# Sheet_3_3v_2020-09-13_15-20-00.net
KiCad netlist of a schematic drawn in Altium Designer
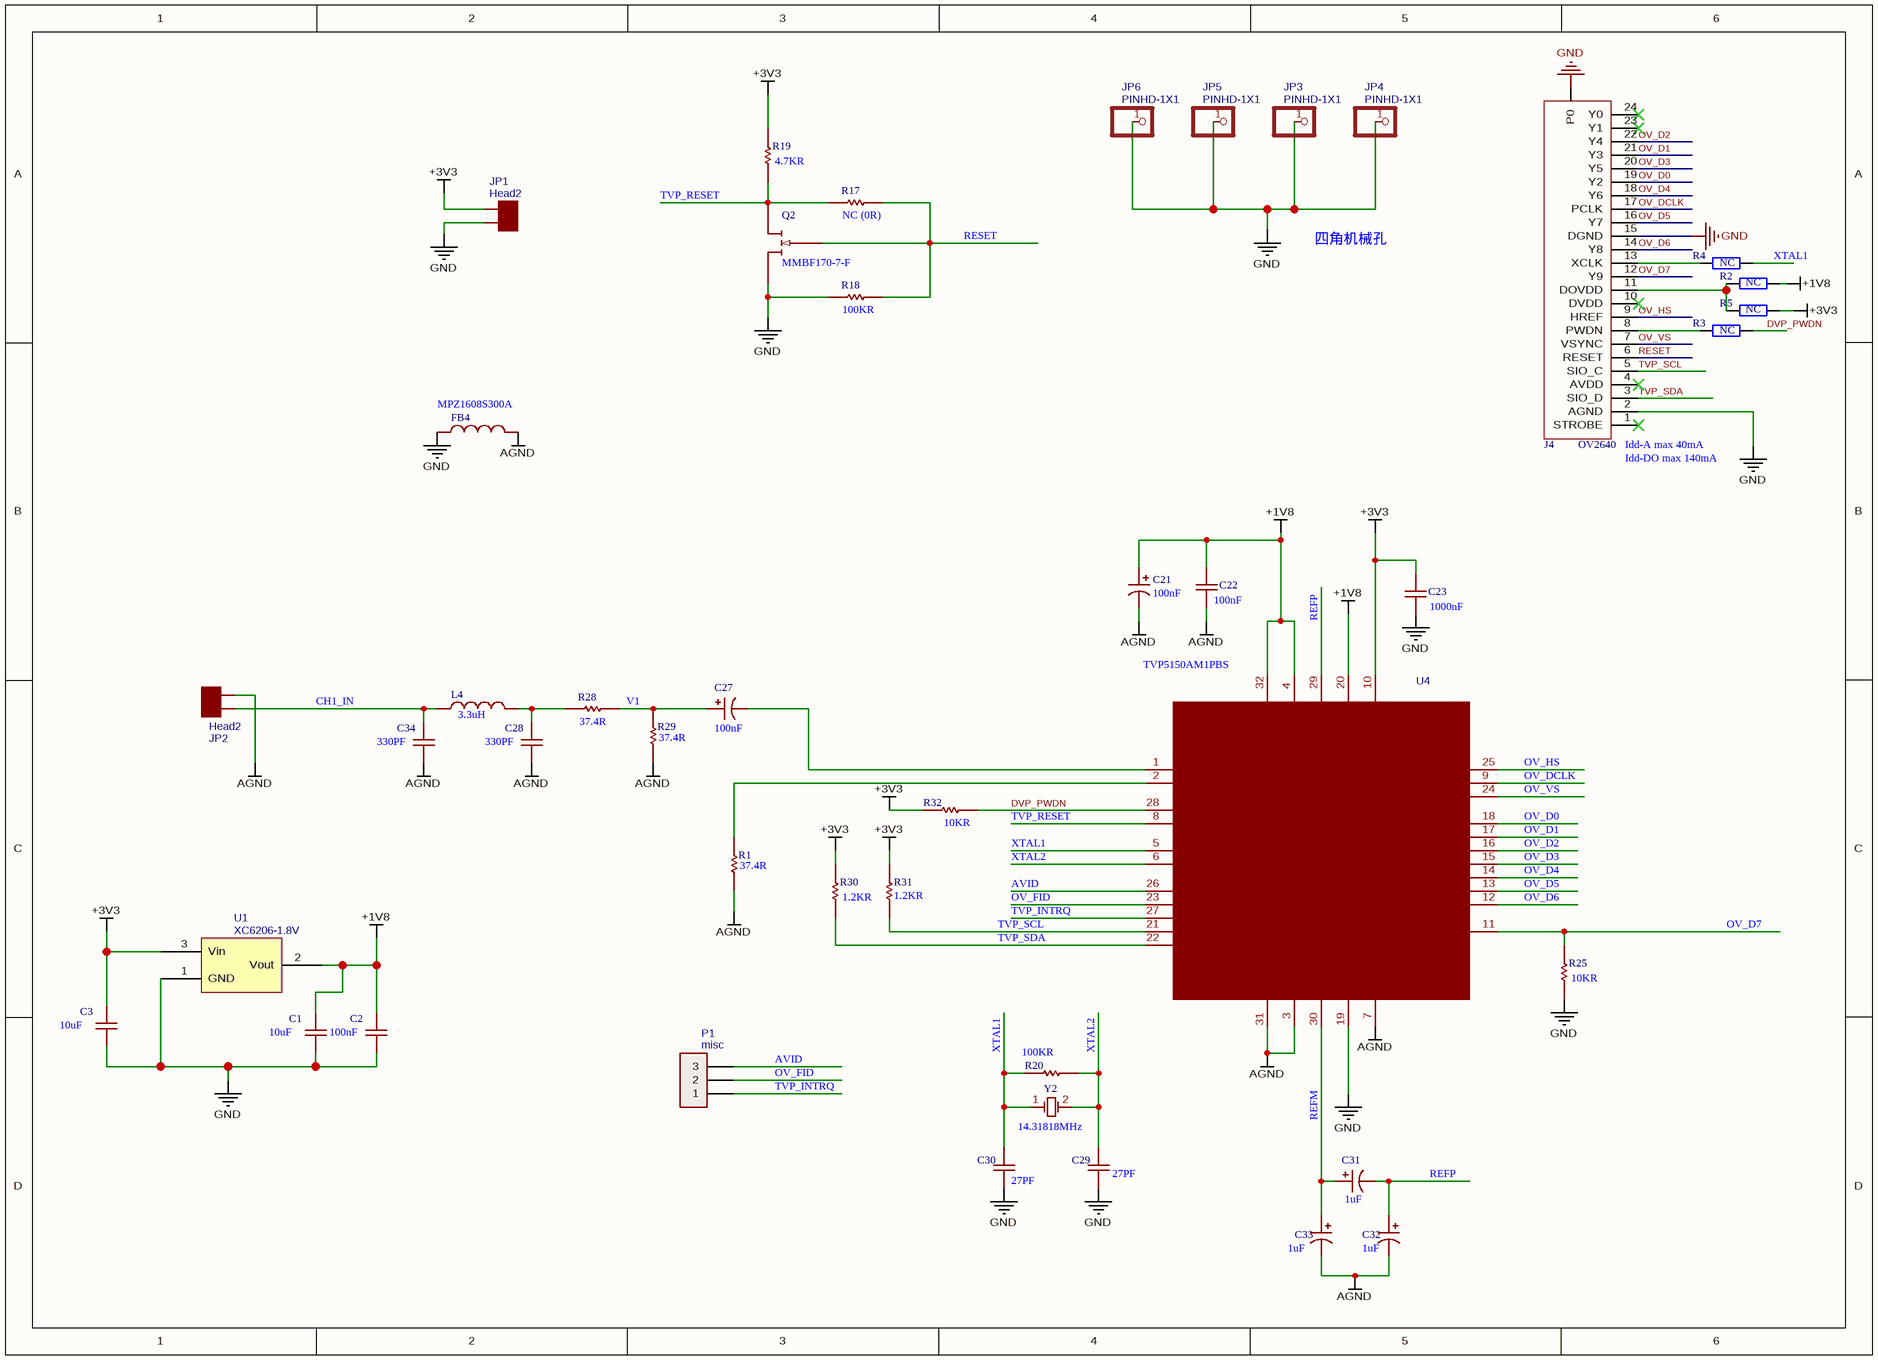
[diagram p0: Sheet_3.3v_2020-09-13_15-20-00.schdoc]

(export (version "E")
  (design (tool "Eeschema 10.0.6"))
  (components
    (comp (ref "C1")
      (value "10uF")
      (fields (field (name "PARTNUMBER") "330PF") (field (name "PUBLISHER") "Altium Limited"))
      (libsource (lib "altium-import") (part "root_1_10uF_"))
    )
    (comp (ref "C2")
      (value "330PF")
      (fields (field (name "PUBLISHER") "Altium Limited"))
      (libsource (lib "altium-import") (part "root_1_330PF_"))
    )
    (comp (ref "C3")
      (value "330PF")
      (fields (field (name "PUBLISHER") "Altium Limited"))
      (libsource (lib "altium-import") (part "root_1_330PF_"))
    )
    (comp (ref "C21")
      (value "100nF")
      (fields
        (field (name "MANUFACTURER") "Vishay or AVX Corporation")
        (field (name "PUBLISHER") "Altium Limited")
      )
      (libsource (lib "altium-import") (part "root_3_100nF_"))
    )
    (comp (ref "C22")
      (value "100nF")
      (fields (field (name "PUBLISHER") "Altium Limited"))
      (libsource (lib "") (part "root_3_100nF__1"))
    )
    (comp (ref "C23")
      (value "1000nF")
      (fields (field (name "PUBLISHER") "Altium Limited"))
      (libsource (lib "altium-import") (part "root_3_1000nF_"))
    )
    (comp (ref "C27")
      (value "100nF")
      (fields
        (field (name "MANUFACTURER") "Vishay or AVX Corporation")
        (field (name "PUBLISHER") "Altium Limited")
      )
      (libsource (lib "altium-import") (part "root_0_100nF_"))
    )
    (comp (ref "C28")
      (value "330PF")
      (fields (field (name "PUBLISHER") "Altium Limited"))
      (libsource (lib "altium-import") (part "root_1_330PF_"))
    )
    (comp (ref "C29")
      (value "27PF")
      (fields (field (name "PUBLISHER") "Altium Limited"))
      (libsource (lib "altium-import") (part "root_1_27PF_"))
    )
    (comp (ref "C30")
      (value "27PF")
      (fields (field (name "PUBLISHER") "Altium Limited"))
      (libsource (lib "altium-import") (part "root_1_27PF_"))
    )
    (comp (ref "C31")
      (value "1uF")
      (fields
        (field (name "MANUFACTURER") "Vishay or AVX Corporation")
        (field (name "PUBLISHER") "Altium Limited")
      )
      (libsource (lib "altium-import") (part "root_0_1uF_"))
    )
    (comp (ref "C32")
      (value "1uF")
      (fields
        (field (name "MANUFACTURER") "Vishay or AVX Corporation")
        (field (name "PUBLISHER") "Altium Limited")
      )
      (libsource (lib "altium-import") (part "root_3_1uF_"))
    )
    (comp (ref "C33")
      (value "1uF")
      (fields
        (field (name "MANUFACTURER") "Vishay or AVX Corporation")
        (field (name "PUBLISHER") "Altium Limited")
      )
      (libsource (lib "altium-import") (part "root_3_1uF_"))
    )
    (comp (ref "C34")
      (value "330PF")
      (fields (field (name "PUBLISHER") "Altium Limited"))
      (libsource (lib "altium-import") (part "root_1_330PF_"))
    )
    (comp (ref "FB4")
      (value "MPZ1608S300A")
      (description "FERRITE BEAD 30 OHM 0603 1LN")
      (fields
        (field (name "MANUFACTURER PART NUMBER") "MPZ1608S300ATAH0")
        (field (name "PUBLISHER") "Altium Limited")
      )
      (libsource (lib "altium-import") (part "root_0_MPZ1608S300A_"))
    )
    (comp (ref "J4")
      (value "OV2640")
      (fields (field (name "PUBLISHER") "Altium Limited"))
      (libsource (lib "altium-import") (part "root_2_OV2640_"))
    )
    (comp (ref "JP1")
      (value "Head2")
      (fields (field (name "CONTRIBUTOR") "395253A"))
      (libsource (lib "altium-import") (part "root_3_Head2_"))
    )
    (comp (ref "JP2")
      (value "Head2")
      (fields (field (name "CONTRIBUTOR") "395253A"))
      (libsource (lib "altium-import") (part "root_1_Head2_"))
    )
    (comp (ref "JP3")
      (value "PINHD-1X1")
      (fields (field (name "CONTRIBUTOR") "Adafruit"))
      (libsource (lib "altium-import") (part "root_0_PINHD-1X1_"))
    )
    (comp (ref "JP4")
      (value "PINHD-1X1")
      (fields (field (name "CONTRIBUTOR") "Adafruit"))
      (libsource (lib "altium-import") (part "root_0_PINHD-1X1_"))
    )
    (comp (ref "JP5")
      (value "PINHD-1X1")
      (fields (field (name "CONTRIBUTOR") "Adafruit"))
      (libsource (lib "altium-import") (part "root_0_PINHD-1X1_"))
    )
    (comp (ref "JP6")
      (value "PINHD-1X1")
      (fields (field (name "CONTRIBUTOR") "Adafruit"))
      (libsource (lib "altium-import") (part "root_0_PINHD-1X1_"))
    )
    (comp (ref "L4")
      (value "3.3uH")
      (fields (field (name "PUBLISHER") "Altium Limited"))
      (libsource (lib "altium-import") (part "root_0_3.3uH_"))
    )
    (comp (ref "P1")
      (value "misc")
      (fields (field (name "BOM_MANUFACTURER PART") "Female header/2.54mm2x3 Female header"))
      (libsource (lib "altium-import") (part "root_2_misc_"))
    )
    (comp (ref "Q2")
      (value "MMBF170-7-F")
      (fields (field (name "MANUFACTURER") "Diodes Incorporated"))
      (libsource (lib "altium-import") (part "root_0_MMBF170-7-F_"))
    )
    (comp (ref "R1")
      (value "37.4R")
      (fields (field (name "PUBLISHER") "Altium Limited"))
      (libsource (lib "altium-import") (part "root_3_37.4R_"))
    )
    (comp (ref "R2") (value "NC") (libsource (lib "altium-import") (part "root_0_NC_")))
    (comp (ref "R3") (value "NC") (libsource (lib "altium-import") (part "root_0_NC_")))
    (comp (ref "R4") (value "NC") (libsource (lib "altium-import") (part "root_0_NC_")))
    (comp (ref "R5") (value "NC") (libsource (lib "altium-import") (part "root_0_NC_")))
    (comp (ref "R17")
      (value "NC (0R)")
      (fields (field (name "PUBLISHER") "Altium Limited"))
      (libsource (lib "altium-import") (part "root_0_NC (0R)_"))
    )
    (comp (ref "R18")
      (value "100KR")
      (fields (field (name "PUBLISHER") "Altium Limited"))
      (libsource (lib "altium-import") (part "root_0_100KR_"))
    )
    (comp (ref "R19")
      (value "4.7KR")
      (fields (field (name "PUBLISHER") "Altium Limited"))
      (libsource (lib "altium-import") (part "root_3_4.7KR_"))
    )
    (comp (ref "R20")
      (value "100KR")
      (fields (field (name "PUBLISHER") "Altium Limited"))
      (libsource (lib "altium-import") (part "root_2_100KR_"))
    )
    (comp (ref "R25")
      (value "10KR")
      (fields (field (name "PUBLISHER") "Altium Limited"))
      (libsource (lib "altium-import") (part "root_3_10KR_"))
    )
    (comp (ref "R28")
      (value "37.4R")
      (fields (field (name "PUBLISHER") "Altium Limited"))
      (libsource (lib "altium-import") (part "root_0_37.4R_"))
    )
    (comp (ref "R29")
      (value "37.4R")
      (fields (field (name "PUBLISHER") "Altium Limited"))
      (libsource (lib "altium-import") (part "root_3_37.4R_"))
    )
    (comp (ref "R30")
      (value "1.2KR")
      (fields (field (name "PUBLISHER") "Altium Limited"))
      (libsource (lib "altium-import") (part "root_3_1.2KR_"))
    )
    (comp (ref "R31")
      (value "1.2KR")
      (fields (field (name "PUBLISHER") "Altium Limited"))
      (libsource (lib "altium-import") (part "root_3_1.2KR_"))
    )
    (comp (ref "R32")
      (value "10KR")
      (fields (field (name "PUBLISHER") "Altium Limited"))
      (libsource (lib "altium-import") (part "root_2_10KR_"))
    )
    (comp (ref "U1")
      (value "XC6206-1.8V")
      (fields (field (name "CONTRIBUTOR") "JesseRock"))
      (libsource (lib "altium-import") (part "root_0_XC6206-1.8V_"))
    )
    (comp (ref "U4")
      (value "TVP5150")
      (fields (field (name "PARTNUMBER") "TVP5150AM1PBS") (field (name "PUBLISHER") "Altium Limited"))
      (libsource (lib "altium-import") (part "root_0_TVP5150_"))
    )
    (comp (ref "Y2")
      (value "14.31818MHz")
      (fields (field (name "MANUFACTURER") "TXC CORPORATION") (field (name "PUBLISHER") "Altium Limited"))
      (libsource (lib "altium-import") (part "root_0_14.31818MHz_"))
    )
  )
  (nets
    (net (code "1") (name "+1V8") (class "Default")
      (node (ref "C1") (pin "2") (pinfunction "2_2") (pintype "passive"))
      (node (ref "C2") (pin "2") (pinfunction "2_2") (pintype "passive"))
      (node (ref "C21") (pin "1") (pinfunction "1_1") (pintype "passive"))
      (node (ref "C22") (pin "1") (pinfunction "1_1") (pintype "passive"))
      (node (ref "R2") (pin "2") (pinfunction "2_2") (pintype "passive"))
      (node (ref "U1") (pin "2") (pinfunction "Vout_2") (pintype "passive"))
      (node (ref "U4") (pin "20") (pinfunction "DVDD_20") (pintype "passive"))
      (node (ref "U4") (pin "32") (pinfunction "CH_AVDD_32") (pintype "passive"))
      (node (ref "U4") (pin "4") (pinfunction "PLL_AVDD_4") (pintype "passive"))
    )
    (net (code "2") (name "+3V3") (class "Default")
      (node (ref "C23") (pin "1") (pinfunction "1_1") (pintype "passive"))
      (node (ref "C3") (pin "2") (pinfunction "2_2") (pintype "passive"))
      (node (ref "JP1") (pin "1") (pinfunction "1_1") (pintype "passive"))
      (node (ref "R19") (pin "1") (pinfunction "1_1") (pintype "passive"))
      (node (ref "R30") (pin "1") (pinfunction "1_1") (pintype "passive"))
      (node (ref "R31") (pin "1") (pinfunction "1_1") (pintype "passive"))
      (node (ref "R32") (pin "2") (pinfunction "2_2") (pintype "passive"))
      (node (ref "R5") (pin "2") (pinfunction "2_2") (pintype "passive"))
      (node (ref "U1") (pin "3") (pinfunction "Vin_3") (pintype "passive"))
      (node (ref "U4") (pin "10") (pinfunction "IO_DVDD_10") (pintype "passive"))
    )
    (net (code "3") (name "/AVID") (class "Default")
      (node (ref "P1") (pin "3") (pinfunction "3_3") (pintype "passive"))
      (node (ref "U4") (pin "26") (pinfunction "AVID_26") (pintype "passive"))
    )
    (net (code "4") (name "/CH1_IN") (class "Default")
      (node (ref "C34") (pin "2") (pinfunction "2_2") (pintype "passive"))
      (node (ref "JP2") (pin "2") (pinfunction "2_2") (pintype "passive"))
      (node (ref "L4") (pin "1") (pinfunction "1_1") (pintype "passive"))
    )
    (net (code "5") (name "/DVP_PWDN") (class "Default")
      (node (ref "R3") (pin "2") (pinfunction "2_2") (pintype "passive"))
      (node (ref "R32") (pin "1") (pinfunction "1_1") (pintype "passive"))
      (node (ref "U4") (pin "28") (pinfunction "PDN_28") (pintype "passive"))
    )
    (net (code "6") (name "/OV_D0") (class "Default")
      (node (ref "J4") (pin "19") (pinfunction "Y2_19") (pintype "passive"))
      (node (ref "U4") (pin "18") (pinfunction "YOUT0_18") (pintype "passive"))
    )
    (net (code "7") (name "/OV_D1") (class "Default")
      (node (ref "J4") (pin "21") (pinfunction "Y3_21") (pintype "passive"))
      (node (ref "U4") (pin "17") (pinfunction "YOUT1_17") (pintype "passive"))
    )
    (net (code "8") (name "/OV_D2") (class "Default")
      (node (ref "J4") (pin "22") (pinfunction "Y4_22") (pintype "passive"))
      (node (ref "U4") (pin "16") (pinfunction "YOUT2_16") (pintype "passive"))
    )
    (net (code "9") (name "/OV_D3") (class "Default")
      (node (ref "J4") (pin "20") (pinfunction "Y5_20") (pintype "passive"))
      (node (ref "U4") (pin "15") (pinfunction "YOUT3_15") (pintype "passive"))
    )
    (net (code "10") (name "/OV_D4") (class "Default")
      (node (ref "J4") (pin "18") (pinfunction "Y6_18") (pintype "passive"))
      (node (ref "U4") (pin "14") (pinfunction "YOUT4_14") (pintype "passive"))
    )
    (net (code "11") (name "/OV_D5") (class "Default")
      (node (ref "J4") (pin "16") (pinfunction "Y7_16") (pintype "passive"))
      (node (ref "U4") (pin "13") (pinfunction "YOUT5_13") (pintype "passive"))
    )
    (net (code "12") (name "/OV_D6") (class "Default")
      (node (ref "J4") (pin "14") (pinfunction "Y8_14") (pintype "passive"))
      (node (ref "U4") (pin "12") (pinfunction "YOUT6_12") (pintype "passive"))
    )
    (net (code "13") (name "/OV_D7") (class "Default")
      (node (ref "J4") (pin "12") (pinfunction "Y9_12") (pintype "passive"))
      (node (ref "R25") (pin "1") (pinfunction "1_1") (pintype "passive"))
      (node (ref "U4") (pin "11") (pinfunction "YOUT7/I2CSEL_11") (pintype "passive"))
    )
    (net (code "14") (name "/OV_DCLK") (class "Default")
      (node (ref "J4") (pin "17") (pinfunction "PCLK_17") (pintype "passive"))
      (node (ref "U4") (pin "9") (pinfunction "PCLK/SCLK_9") (pintype "passive"))
    )
    (net (code "15") (name "/OV_FID") (class "Default")
      (node (ref "P1") (pin "2") (pinfunction "2_2") (pintype "passive"))
      (node (ref "U4") (pin "23") (pinfunction "FID/GLCO_23") (pintype "passive"))
    )
    (net (code "16") (name "/OV_HS") (class "Default")
      (node (ref "J4") (pin "9") (pinfunction "HREF_9") (pintype "passive"))
      (node (ref "U4") (pin "25") (pinfunction "HSYNC_25") (pintype "passive"))
    )
    (net (code "17") (name "/OV_VS") (class "Default")
      (node (ref "J4") (pin "7") (pinfunction "VSYNC_7") (pintype "passive"))
      (node (ref "U4") (pin "24") (pinfunction "VSYNC/PALI_24") (pintype "passive"))
    )
    (net (code "18") (name "/REFM") (class "Default")
      (node (ref "C31") (pin "1") (pinfunction "1_1") (pintype "passive"))
      (node (ref "C33") (pin "1") (pinfunction "1_1") (pintype "passive"))
      (node (ref "U4") (pin "30") (pinfunction "REFM_30") (pintype "passive"))
    )
    (net (code "19") (name "/REFP") (class "Default")
      (node (ref "C31") (pin "2") (pinfunction "2_2") (pintype "passive"))
      (node (ref "C32") (pin "1") (pinfunction "1_1") (pintype "passive"))
      (node (ref "U4") (pin "29") (pinfunction "REFP_29") (pintype "passive"))
    )
    (net (code "20") (name "/RESET") (class "Default")
      (node (ref "J4") (pin "6") (pinfunction "RESET_6") (pintype "passive"))
      (node (ref "Q2") (pin "1") (pinfunction "G_1") (pintype "passive"))
      (node (ref "R17") (pin "2") (pinfunction "2_2") (pintype "passive"))
      (node (ref "R18") (pin "2") (pinfunction "2_2") (pintype "passive"))
    )
    (net (code "21") (name "/TVP_INTRQ") (class "Default")
      (node (ref "P1") (pin "1") (pinfunction "1_1") (pintype "passive"))
      (node (ref "U4") (pin "27") (pinfunction "INTREQ/GPCL/VBLK_27") (pintype "passive"))
    )
    (net (code "22") (name "/TVP_RESET") (class "Default")
      (node (ref "Q2") (pin "3") (pinfunction "D_3") (pintype "passive"))
      (node (ref "R17") (pin "1") (pinfunction "1_1") (pintype "passive"))
      (node (ref "R19") (pin "2") (pinfunction "2_2") (pintype "passive"))
      (node (ref "U4") (pin "8") (pinfunction "RESETB_8") (pintype "passive"))
    )
    (net (code "23") (name "/TVP_SCL") (class "Default")
      (node (ref "J4") (pin "5") (pinfunction "SIO_C_5") (pintype "passive"))
      (node (ref "R31") (pin "2") (pinfunction "2_2") (pintype "passive"))
      (node (ref "U4") (pin "21") (pinfunction "SCL_21") (pintype "passive"))
    )
    (net (code "24") (name "/TVP_SDA") (class "Default")
      (node (ref "J4") (pin "3") (pinfunction "SIO_D_3") (pintype "passive"))
      (node (ref "R30") (pin "2") (pinfunction "2_2") (pintype "passive"))
      (node (ref "U4") (pin "22") (pinfunction "SDA_22") (pintype "passive"))
    )
    (net (code "25") (name "/V1") (class "Default")
      (node (ref "C27") (pin "1") (pinfunction "1_1") (pintype "passive"))
      (node (ref "R28") (pin "2") (pinfunction "2_2") (pintype "passive"))
      (node (ref "R29") (pin "1") (pinfunction "1_1") (pintype "passive"))
    )
    (net (code "26") (name "/XTAL1") (class "Default")
      (node (ref "C30") (pin "2") (pinfunction "2_2") (pintype "passive"))
      (node (ref "R20") (pin "2") (pinfunction "2_2") (pintype "passive"))
      (node (ref "R4") (pin "2") (pinfunction "2_2") (pintype "passive"))
      (node (ref "U4") (pin "5") (pinfunction "XTAL1/OSC_5") (pintype "passive"))
      (node (ref "Y2") (pin "1") (pinfunction "OSC1_1") (pintype "passive"))
    )
    (net (code "27") (name "/XTAL2") (class "Default")
      (node (ref "C29") (pin "2") (pinfunction "2_2") (pintype "passive"))
      (node (ref "R20") (pin "1") (pinfunction "1_1") (pintype "passive"))
      (node (ref "U4") (pin "6") (pinfunction "XTAL2_6") (pintype "passive"))
      (node (ref "Y2") (pin "2") (pinfunction "OSC2_2") (pintype "passive"))
    )
    (net (code "28") (name "AGND") (class "Default")
      (node (ref "C21") (pin "2") (pinfunction "2_2") (pintype "passive"))
      (node (ref "C22") (pin "2") (pinfunction "2_2") (pintype "passive"))
      (node (ref "C28") (pin "1") (pinfunction "1_1") (pintype "passive"))
      (node (ref "C32") (pin "2") (pinfunction "2_2") (pintype "passive"))
      (node (ref "C33") (pin "2") (pinfunction "2_2") (pintype "passive"))
      (node (ref "C34") (pin "1") (pinfunction "1_1") (pintype "passive"))
      (node (ref "FB4") (pin "2") (pinfunction "2_2") (pintype "passive"))
      (node (ref "JP2") (pin "1") (pinfunction "1_1") (pintype "passive"))
      (node (ref "R1") (pin "2") (pinfunction "2_2") (pintype "passive"))
      (node (ref "R29") (pin "2") (pinfunction "2_2") (pintype "passive"))
      (node (ref "U4") (pin "3") (pinfunction "PLL_AGND_3") (pintype "passive"))
      (node (ref "U4") (pin "31") (pinfunction "CH_AGND_31") (pintype "passive"))
      (node (ref "U4") (pin "7") (pinfunction "AGND_7") (pintype "passive"))
    )
    (net (code "29") (name "GND") (class "Default")
      (node (ref "C1") (pin "1") (pinfunction "1_1") (pintype "passive"))
      (node (ref "C2") (pin "1") (pinfunction "1_1") (pintype "passive"))
      (node (ref "C23") (pin "2") (pinfunction "2_2") (pintype "passive"))
      (node (ref "C29") (pin "1") (pinfunction "1_1") (pintype "passive"))
      (node (ref "C3") (pin "1") (pinfunction "1_1") (pintype "passive"))
      (node (ref "C30") (pin "1") (pinfunction "1_1") (pintype "passive"))
      (node (ref "FB4") (pin "1") (pinfunction "1_1") (pintype "passive"))
      (node (ref "J4") (pin "15") (pinfunction "DGND_15") (pintype "passive"))
      (node (ref "J4") (pin "2") (pinfunction "AGND_2") (pintype "passive"))
      (node (ref "J4") (pin "P0") (pinfunction "P0_P0") (pintype "passive"))
      (node (ref "JP1") (pin "2") (pinfunction "2_2") (pintype "passive"))
      (node (ref "JP3") (pin "1") (pinfunction "1_1") (pintype "passive"))
      (node (ref "JP4") (pin "1") (pinfunction "1_1") (pintype "passive"))
      (node (ref "JP5") (pin "1") (pinfunction "1_1") (pintype "passive"))
      (node (ref "JP6") (pin "1") (pinfunction "1_1") (pintype "passive"))
      (node (ref "Q2") (pin "2") (pinfunction "S_2") (pintype "passive"))
      (node (ref "R18") (pin "1") (pinfunction "1_1") (pintype "passive"))
      (node (ref "R25") (pin "2") (pinfunction "2_2") (pintype "passive"))
      (node (ref "U1") (pin "1") (pinfunction "GND_1") (pintype "passive"))
      (node (ref "U4") (pin "19") (pinfunction "DGND_19") (pintype "passive"))
    )
    (net (code "30") (name "Net-(C28-Pad2)") (class "Default")
      (node (ref "C28") (pin "2") (pinfunction "2_2") (pintype "passive"))
      (node (ref "L4") (pin "2") (pinfunction "2_2") (pintype "passive"))
      (node (ref "R28") (pin "1") (pinfunction "1_1") (pintype "passive"))
    )
    (net (code "31") (name "Net-(J4-DOVDD)") (class "Default")
      (node (ref "J4") (pin "11") (pinfunction "DOVDD_11") (pintype "passive"))
      (node (ref "R2") (pin "1") (pinfunction "1_1") (pintype "passive"))
      (node (ref "R5") (pin "1") (pinfunction "1_1") (pintype "passive"))
    )
    (net (code "32") (name "Net-(J4-PWDN)") (class "Default")
      (node (ref "J4") (pin "8") (pinfunction "PWDN_8") (pintype "passive"))
      (node (ref "R3") (pin "1") (pinfunction "1_1") (pintype "passive"))
    )
    (net (code "33") (name "Net-(J4-XCLK)") (class "Default")
      (node (ref "J4") (pin "13") (pinfunction "XCLK_13") (pintype "passive"))
      (node (ref "R4") (pin "1") (pinfunction "1_1") (pintype "passive"))
    )
    (net (code "34") (name "Net-(U4-AIP1A)") (class "Default")
      (node (ref "C27") (pin "2") (pinfunction "2_2") (pintype "passive"))
      (node (ref "U4") (pin "1") (pinfunction "AIP1A_1") (pintype "passive"))
    )
    (net (code "35") (name "Net-(U4-AIP1B)") (class "Default")
      (node (ref "R1") (pin "1") (pinfunction "1_1") (pintype "passive"))
      (node (ref "U4") (pin "2") (pinfunction "AIP1B_2") (pintype "passive"))
    )
    (net (code "36") (name "unconnected-(J4-AVDD-Pad4)") (class "Default")
      (node (ref "J4") (pin "4") (pinfunction "AVDD_4") (pintype "passive+no_connect"))
    )
    (net (code "37") (name "unconnected-(J4-DVDD-Pad10)") (class "Default")
      (node (ref "J4") (pin "10") (pinfunction "DVDD_10") (pintype "passive+no_connect"))
    )
    (net (code "38") (name "unconnected-(J4-STROBE-Pad1)") (class "Default")
      (node (ref "J4") (pin "1") (pinfunction "STROBE_1") (pintype "passive+no_connect"))
    )
    (net (code "39") (name "unconnected-(J4-Y0-Pad24)") (class "Default")
      (node (ref "J4") (pin "24") (pinfunction "Y0_24") (pintype "passive+no_connect"))
    )
    (net (code "40") (name "unconnected-(J4-Y1-Pad23)") (class "Default")
      (node (ref "J4") (pin "23") (pinfunction "Y1_23") (pintype "passive+no_connect"))
    )
  )
)
